# Olimex_ESP32_POE_Wing.net
KiCad netlist of a schematic drawn in EAGLE
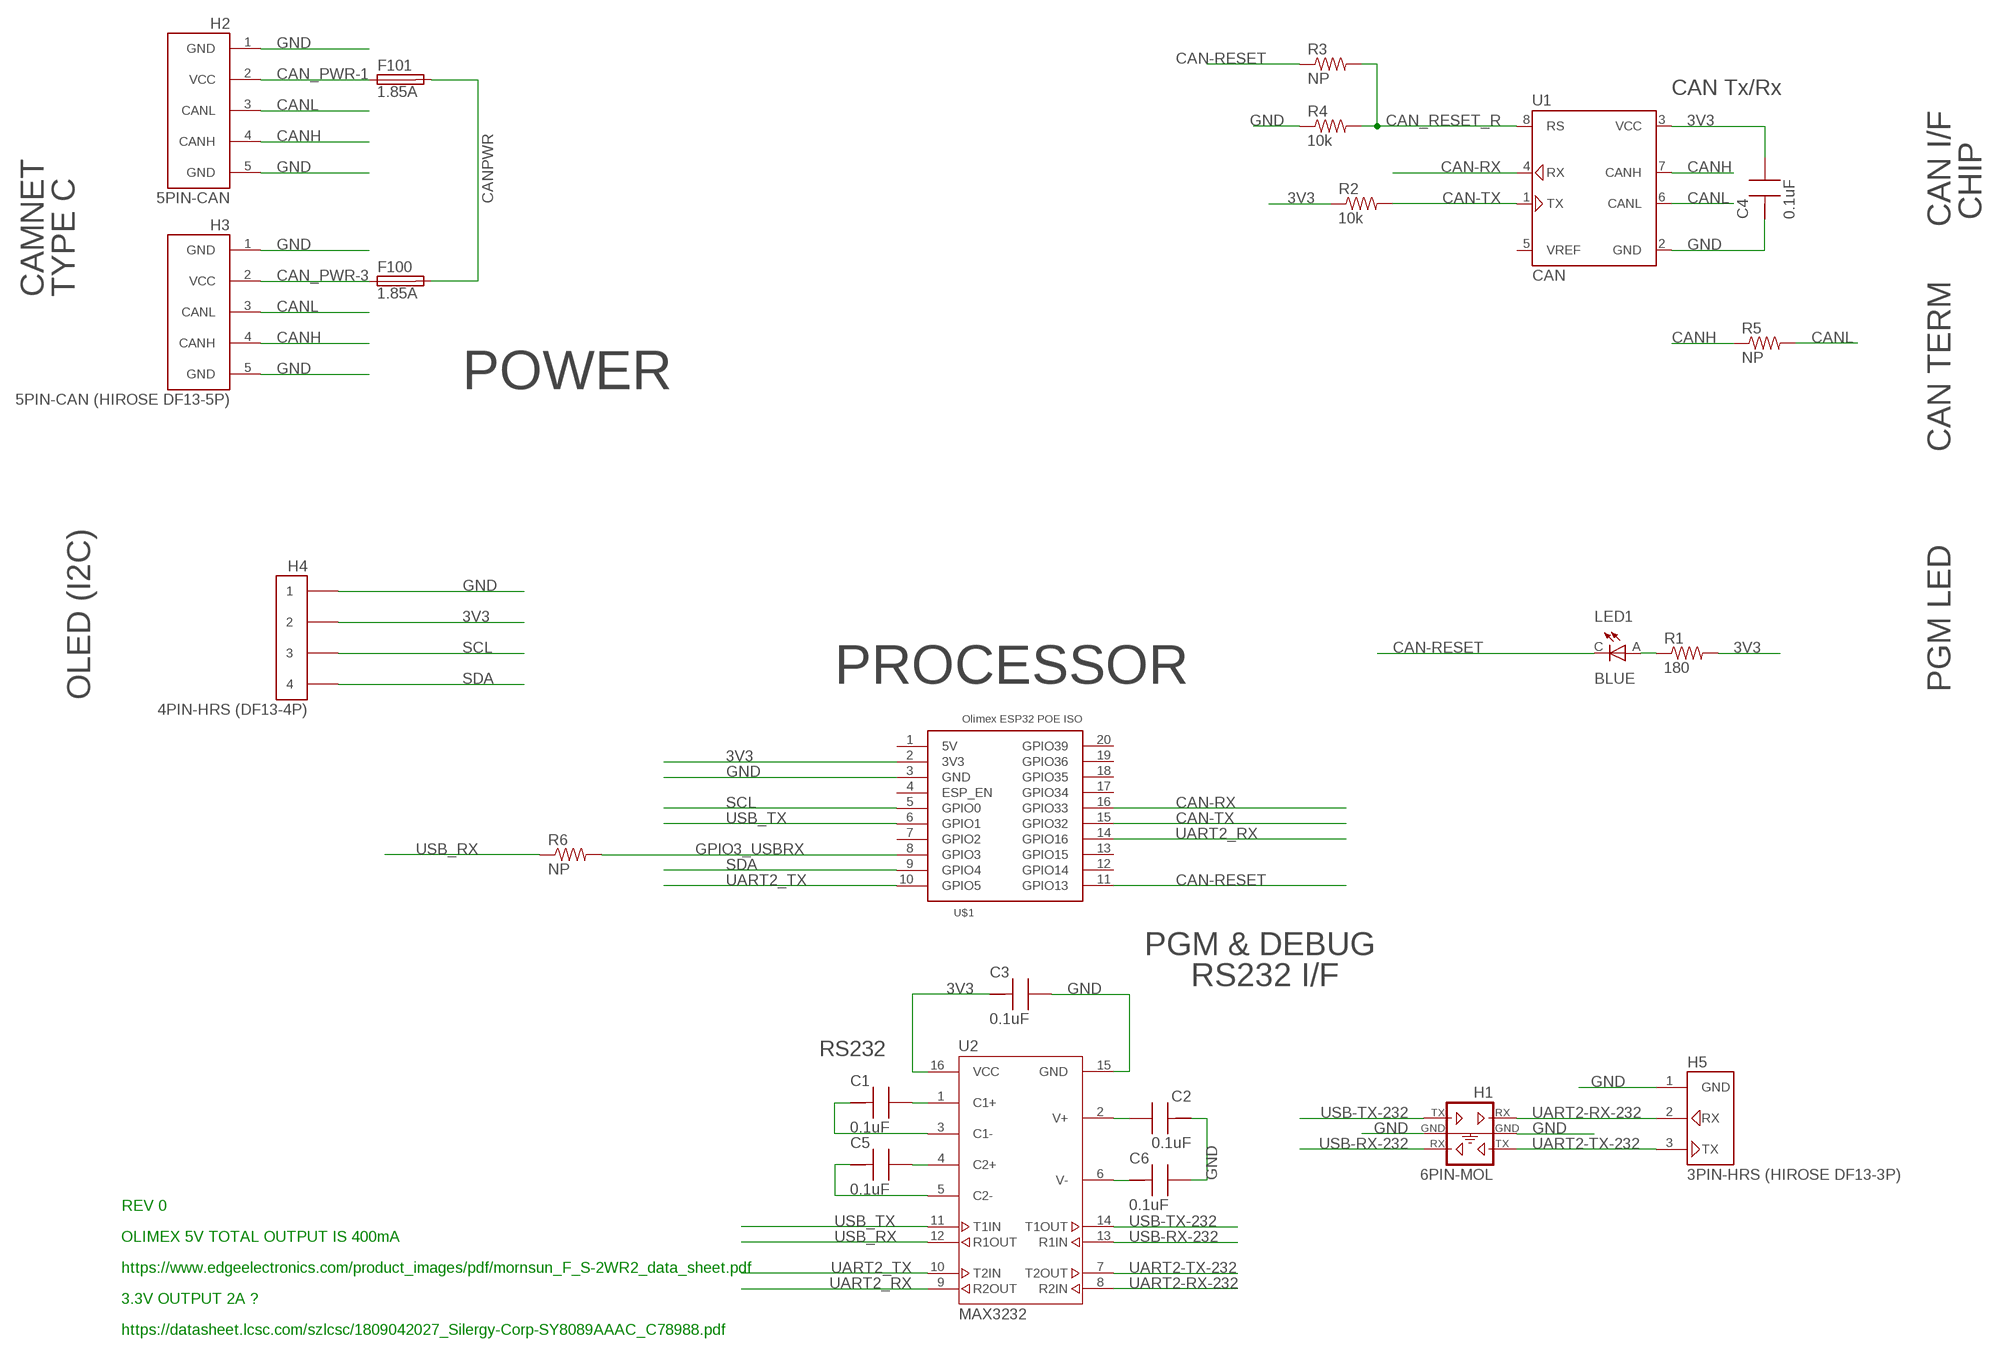
[diagram p0: schematic, sheet 1]

(export (version "E")
  (design (tool "Eeschema 10.0.6"))
  (components
    (comp (ref "C1")
      (value "0.1uF")
      (footprint "eagle-import:C0805")
      (libsource (lib "eagle-import") (part "C-USC0805"))
    )
    (comp (ref "C2")
      (value "0.1uF")
      (footprint "eagle-import:C0805")
      (libsource (lib "eagle-import") (part "C-USC0805"))
    )
    (comp (ref "C3")
      (value "0.1uF")
      (footprint "eagle-import:C0805")
      (libsource (lib "eagle-import") (part "C-USC0805"))
    )
    (comp (ref "C4")
      (value "0.1uF")
      (footprint "eagle-import:C0805")
      (libsource (lib "eagle-import") (part "C-USC0805"))
    )
    (comp (ref "C5")
      (value "0.1uF")
      (footprint "eagle-import:C0805")
      (libsource (lib "eagle-import") (part "C-USC0805"))
    )
    (comp (ref "C6")
      (value "0.1uF")
      (footprint "eagle-import:C0805")
      (libsource (lib "eagle-import") (part "C-USC0805"))
    )
    (comp (ref "F100")
      (value "1.85A")
      (footprint "eagle-import:2920")
      (libsource (lib "eagle-import") (part "BEL-OZCD"))
    )
    (comp (ref "F101")
      (value "1.85A")
      (footprint "eagle-import:2920")
      (libsource (lib "eagle-import") (part "BEL-OZCD"))
    )
    (comp (ref "H1")
      (value "6PIN-MOL")
      (footprint "eagle-import:87831-0620")
      (libsource (lib "eagle-import") (part "6PIN-PGM-2MMVTH"))
    )
    (comp (ref "H2")
      (value "5PIN-CAN")
      (footprint "eagle-import:DF13-5P-1.25DSA")
      (libsource (lib "eagle-import") (part "5PIN-CAN-1.25MMVTH"))
    )
    (comp (ref "H3")
      (value "5PIN-CAN (HIROSE DF13-5P)")
      (footprint "eagle-import:DF13-5P-1.25DSA")
      (libsource (lib "eagle-import") (part "5PIN-CAN-1.25MMVTH"))
    )
    (comp (ref "H4")
      (value "4PIN-HRS (DF13-4P)")
      (footprint "eagle-import:DF13-4P-1.25DSA")
      (libsource (lib "eagle-import") (part "DF13-4P-1.25VTH"))
    )
    (comp (ref "H5")
      (value "3PIN-HRS (HIROSE DF13-3P)")
      (footprint "eagle-import:DF13-3P-1.25DSA")
      (libsource (lib "eagle-import") (part "3PIN-PGM-1.25MMVTH"))
    )
    (comp (ref "LED1")
      (value "BLUE")
      (footprint "eagle-import:CHIPLED_0805")
      (libsource (lib "eagle-import") (part "LED805SMT"))
    )
    (comp (ref "R1")
      (value "180")
      (footprint "eagle-import:R0805")
      (libsource (lib "eagle-import") (part "R-US_R0805"))
    )
    (comp (ref "R2")
      (value "10k")
      (footprint "eagle-import:R0805")
      (libsource (lib "eagle-import") (part "R-US_R0805"))
    )
    (comp (ref "R3")
      (value "NP")
      (footprint "eagle-import:R0805")
      (libsource (lib "eagle-import") (part "R-US_R0805"))
    )
    (comp (ref "R4")
      (value "10k")
      (footprint "eagle-import:R0805")
      (libsource (lib "eagle-import") (part "R-US_R0805"))
    )
    (comp (ref "R5")
      (value "NP")
      (footprint "eagle-import:R0805")
      (libsource (lib "eagle-import") (part "R-US_R0805"))
    )
    (comp (ref "R6")
      (value "NP")
      (footprint "eagle-import:R0805")
      (libsource (lib "eagle-import") (part "R-US_R0805"))
    )
    (comp (ref "U$1")
      (value "OLIMEX_POE_ISOPOEISO")
      (footprint "eagle-import:OLIMEX_POE_ISO")
      (libsource (lib "eagle-import") (part "OLIMEX_POE_ISOPOEISO"))
    )
    (comp (ref "U1")
      (value "CAN")
      (footprint "eagle-import:SO-08")
      (libsource (lib "eagle-import") (part "SN65HVD230DR"))
    )
    (comp (ref "U2")
      (value "MAX3232")
      (footprint "eagle-import:TSSOP16")
      (libsource (lib "eagle-import") (part "MAX3232TSSOP16"))
    )
  )
  (nets
    (net (code "1") (name "/3V3") (class "Default")
      (node (ref "C3") (pin "2") (pinfunction "-_2") (pintype "passive"))
      (node (ref "C4") (pin "1") (pinfunction "+_1") (pintype "passive"))
      (node (ref "H4") (pin "2") (pinfunction "2_2") (pintype "passive"))
      (node (ref "R1") (pin "2") (pinfunction "2_2") (pintype "passive"))
      (node (ref "R2") (pin "1") (pinfunction "1_1") (pintype "passive"))
      (node (ref "U$1") (pin "2") (pinfunction "3V3_2") (pintype "power_in"))
      (node (ref "U1") (pin "3") (pinfunction "VCC_3") (pintype "power_in"))
      (node (ref "U2") (pin "16") (pinfunction "VCC_16") (pintype "power_in"))
    )
    (net (code "2") (name "/5V") (class "Default")
      (node (ref "U$1") (pin "1") (pinfunction "5V_1") (pintype "power_in"))
    )
    (net (code "3") (name "/CAN-RESET") (class "Default")
      (node (ref "LED1") (pin "C") (pinfunction "C_C") (pintype "passive"))
      (node (ref "R3") (pin "1") (pinfunction "1_1") (pintype "passive"))
      (node (ref "U$1") (pin "11") (pinfunction "GPIO13_11") (pintype "bidirectional"))
    )
    (net (code "4") (name "/CAN-RX") (class "Default")
      (node (ref "U$1") (pin "16") (pinfunction "GPIO33_16") (pintype "bidirectional"))
      (node (ref "U1") (pin "4") (pinfunction "RX_4") (pintype "output"))
    )
    (net (code "5") (name "/CAN-TX") (class "Default")
      (node (ref "R2") (pin "2") (pinfunction "2_2") (pintype "passive"))
      (node (ref "U$1") (pin "15") (pinfunction "GPIO32_15") (pintype "bidirectional"))
      (node (ref "U1") (pin "1") (pinfunction "TX_1") (pintype "input"))
    )
    (net (code "6") (name "/CANH") (class "Default")
      (node (ref "H2") (pin "4") (pinfunction "CANH_4") (pintype "passive"))
      (node (ref "H3") (pin "4") (pinfunction "CANH_4") (pintype "passive"))
      (node (ref "R5") (pin "1") (pinfunction "1_1") (pintype "passive"))
      (node (ref "U1") (pin "7") (pinfunction "CANH_7") (pintype "bidirectional"))
    )
    (net (code "7") (name "/CANL") (class "Default")
      (node (ref "H2") (pin "3") (pinfunction "CANL_3") (pintype "passive"))
      (node (ref "H3") (pin "3") (pinfunction "CANL_3") (pintype "passive"))
      (node (ref "R5") (pin "2") (pinfunction "2_2") (pintype "passive"))
      (node (ref "U1") (pin "6") (pinfunction "CANL_6") (pintype "bidirectional"))
    )
    (net (code "8") (name "/CANPWR") (class "Default")
      (node (ref "F100") (pin "P2") (pinfunction "2_P2") (pintype "passive"))
      (node (ref "F101") (pin "P2") (pinfunction "2_P2") (pintype "passive"))
    )
    (net (code "9") (name "/CAN_PWR-1") (class "Default")
      (node (ref "F101") (pin "P1") (pinfunction "1_P1") (pintype "passive"))
      (node (ref "H2") (pin "2") (pinfunction "VCC_2") (pintype "power_in"))
    )
    (net (code "10") (name "/CAN_PWR-3") (class "Default")
      (node (ref "F100") (pin "P1") (pinfunction "1_P1") (pintype "passive"))
      (node (ref "H3") (pin "2") (pinfunction "VCC_2") (pintype "power_in"))
    )
    (net (code "11") (name "/CAN_RESET_R") (class "Default")
      (node (ref "R3") (pin "2") (pinfunction "2_2") (pintype "passive"))
      (node (ref "R4") (pin "2") (pinfunction "2_2") (pintype "passive"))
      (node (ref "U1") (pin "8") (pinfunction "RS_8") (pintype "input"))
    )
    (net (code "12") (name "/GND") (class "Default")
      (node (ref "C2") (pin "2") (pinfunction "-_2") (pintype "passive"))
      (node (ref "C3") (pin "1") (pinfunction "+_1") (pintype "passive"))
      (node (ref "C4") (pin "2") (pinfunction "-_2") (pintype "passive"))
      (node (ref "C6") (pin "1") (pinfunction "+_1") (pintype "passive"))
      (node (ref "H1") (pin "3") (pinfunction "3_3") (pintype "passive"))
      (node (ref "H1") (pin "4") (pinfunction "4_4") (pintype "passive"))
      (node (ref "H2") (pin "1") (pinfunction "GND_1") (pintype "power_in"))
      (node (ref "H2") (pin "5") (pinfunction "GND_5") (pintype "power_in"))
      (node (ref "H3") (pin "1") (pinfunction "GND_1") (pintype "power_in"))
      (node (ref "H3") (pin "5") (pinfunction "GND_5") (pintype "power_in"))
      (node (ref "H4") (pin "1") (pinfunction "1_1") (pintype "passive"))
      (node (ref "H5") (pin "1") (pinfunction "GND_1") (pintype "power_in"))
      (node (ref "R4") (pin "1") (pinfunction "1_1") (pintype "passive"))
      (node (ref "U$1") (pin "3") (pinfunction "GND_3") (pintype "power_in"))
      (node (ref "U1") (pin "2") (pinfunction "GND_2") (pintype "power_in"))
      (node (ref "U2") (pin "15") (pinfunction "GND_15") (pintype "power_in"))
    )
    (net (code "13") (name "/GPIO3_USBRX") (class "Default")
      (node (ref "R6") (pin "2") (pinfunction "2_2") (pintype "passive"))
      (node (ref "U$1") (pin "8") (pinfunction "GPIO3_8") (pintype "bidirectional"))
    )
    (net (code "14") (name "/SCL") (class "Default")
      (node (ref "H4") (pin "3") (pinfunction "3_3") (pintype "passive"))
      (node (ref "U$1") (pin "5") (pinfunction "GPIO0_5") (pintype "bidirectional"))
    )
    (net (code "15") (name "/SDA") (class "Default")
      (node (ref "H4") (pin "4") (pinfunction "4_4") (pintype "passive"))
      (node (ref "U$1") (pin "9") (pinfunction "GPIO4_9") (pintype "bidirectional"))
    )
    (net (code "16") (name "/UART2-RX-232") (class "Default")
      (node (ref "H1") (pin "1") (pinfunction "1_1") (pintype "passive"))
      (node (ref "H5") (pin "2") (pinfunction "RX_2") (pintype "output"))
      (node (ref "U2") (pin "8") (pinfunction "R2IN_8") (pintype "input"))
    )
    (net (code "17") (name "/UART2-TX-232") (class "Default")
      (node (ref "H1") (pin "5") (pinfunction "5_5") (pintype "passive"))
      (node (ref "H5") (pin "3") (pinfunction "TX_3") (pintype "input"))
      (node (ref "U2") (pin "7") (pinfunction "T2OUT_7") (pintype "output"))
    )
    (net (code "18") (name "/UART2_RX") (class "Default")
      (node (ref "U$1") (pin "14") (pinfunction "GPIO16_14") (pintype "bidirectional"))
      (node (ref "U2") (pin "9") (pinfunction "R2OUT_9") (pintype "output"))
    )
    (net (code "19") (name "/UART2_TX") (class "Default")
      (node (ref "U$1") (pin "10") (pinfunction "GPIO5_10") (pintype "bidirectional"))
      (node (ref "U2") (pin "10") (pinfunction "T2IN_10") (pintype "input"))
    )
    (net (code "20") (name "/USB-RX-232") (class "Default")
      (node (ref "H1") (pin "6") (pinfunction "6_6") (pintype "passive"))
      (node (ref "U2") (pin "13") (pinfunction "R1IN_13") (pintype "input"))
    )
    (net (code "21") (name "/USB-TX-232") (class "Default")
      (node (ref "H1") (pin "2") (pinfunction "2_2") (pintype "passive"))
      (node (ref "U2") (pin "14") (pinfunction "T1OUT_14") (pintype "output"))
    )
    (net (code "22") (name "/USB_RX") (class "Default")
      (node (ref "R6") (pin "1") (pinfunction "1_1") (pintype "passive"))
      (node (ref "U2") (pin "12") (pinfunction "R1OUT_12") (pintype "output"))
    )
    (net (code "23") (name "/USB_TX") (class "Default")
      (node (ref "U$1") (pin "6") (pinfunction "GPIO1_6") (pintype "bidirectional"))
      (node (ref "U2") (pin "11") (pinfunction "T1IN_11") (pintype "input"))
    )
    (net (code "24") (name "Net-(C1-+)") (class "Default")
      (node (ref "C1") (pin "1") (pinfunction "+_1") (pintype "passive"))
      (node (ref "U2") (pin "1") (pinfunction "C1+_1") (pintype "passive"))
    )
    (net (code "25") (name "Net-(C1--)") (class "Default")
      (node (ref "C1") (pin "2") (pinfunction "-_2") (pintype "passive"))
      (node (ref "U2") (pin "3") (pinfunction "C1-_3") (pintype "passive"))
    )
    (net (code "26") (name "Net-(C2-+)") (class "Default")
      (node (ref "C2") (pin "1") (pinfunction "+_1") (pintype "passive"))
      (node (ref "U2") (pin "2") (pinfunction "V+_2") (pintype "passive"))
    )
    (net (code "27") (name "Net-(C5-+)") (class "Default")
      (node (ref "C5") (pin "1") (pinfunction "+_1") (pintype "passive"))
      (node (ref "U2") (pin "4") (pinfunction "C2+_4") (pintype "passive"))
    )
    (net (code "28") (name "Net-(C5--)") (class "Default")
      (node (ref "C5") (pin "2") (pinfunction "-_2") (pintype "passive"))
      (node (ref "U2") (pin "5") (pinfunction "C2-_5") (pintype "passive"))
    )
    (net (code "29") (name "Net-(C6--)") (class "Default")
      (node (ref "C6") (pin "2") (pinfunction "-_2") (pintype "passive"))
      (node (ref "U2") (pin "6") (pinfunction "V-_6") (pintype "passive"))
    )
    (net (code "30") (name "Net-(LED1-PadA)") (class "Default")
      (node (ref "LED1") (pin "A") (pinfunction "A_A") (pintype "passive"))
      (node (ref "R1") (pin "1") (pinfunction "1_1") (pintype "passive"))
    )
    (net (code "31") (name "unconnected-(U$1-ESP_EN-Pad4)") (class "Default")
      (node (ref "U$1") (pin "4") (pinfunction "ESP_EN_4") (pintype "bidirectional"))
    )
    (net (code "32") (name "unconnected-(U$1-GPIO2-Pad7)") (class "Default")
      (node (ref "U$1") (pin "7") (pinfunction "GPIO2_7") (pintype "bidirectional"))
    )
    (net (code "33") (name "unconnected-(U$1-GPIO14-Pad12)") (class "Default")
      (node (ref "U$1") (pin "12") (pinfunction "GPIO14_12") (pintype "bidirectional"))
    )
    (net (code "34") (name "unconnected-(U$1-GPIO15-Pad13)") (class "Default")
      (node (ref "U$1") (pin "13") (pinfunction "GPIO15_13") (pintype "bidirectional"))
    )
    (net (code "35") (name "unconnected-(U$1-GPIO34-Pad17)") (class "Default")
      (node (ref "U$1") (pin "17") (pinfunction "GPIO34_17") (pintype "input"))
    )
    (net (code "36") (name "unconnected-(U$1-GPIO35-Pad18)") (class "Default")
      (node (ref "U$1") (pin "18") (pinfunction "GPIO35_18") (pintype "input"))
    )
    (net (code "37") (name "unconnected-(U$1-GPIO36-Pad19)") (class "Default")
      (node (ref "U$1") (pin "19") (pinfunction "GPIO36_19") (pintype "input"))
    )
    (net (code "38") (name "unconnected-(U$1-GPIO39-Pad20)") (class "Default")
      (node (ref "U$1") (pin "20") (pinfunction "GPIO39_20") (pintype "input"))
    )
    (net (code "39") (name "unconnected-(U1-VREF-Pad5)") (class "Default")
      (node (ref "U1") (pin "5") (pinfunction "VREF_5") (pintype "output"))
    )
  )
)
